# connectors.net
KiCad netlist of a schematic drawn in EAGLE
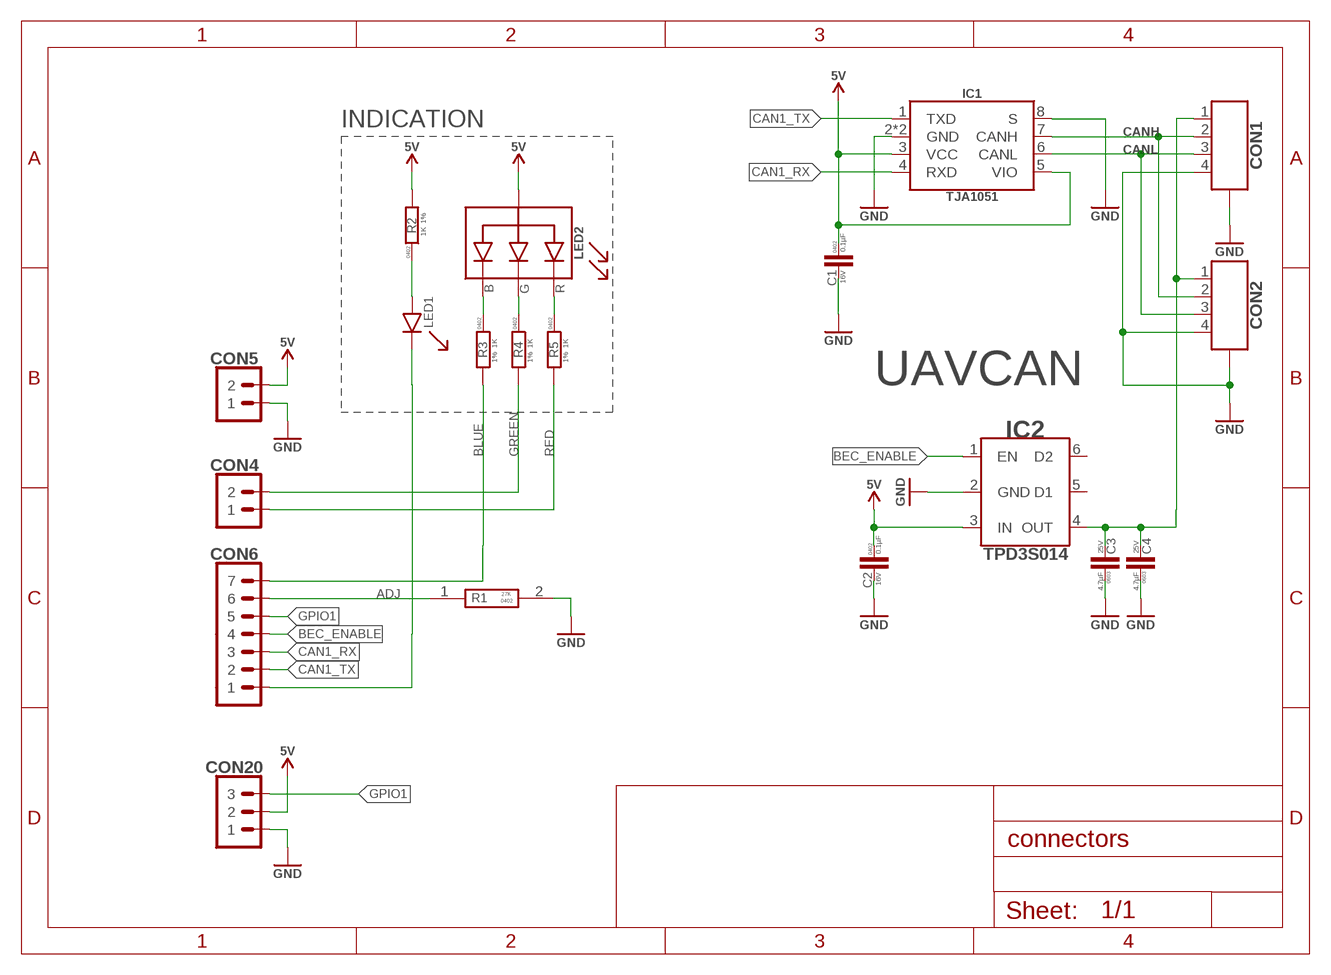
[diagram p0: schematic, sheet 1]

(export (version "E")
  (design (tool "Eeschema 10.0.6"))
  (components
    (comp (ref "C1")
      (value "0.1µF")
      (footprint "eagle-import:C0402")
      (fields
        (field (name "MANF") "Murata Electronics North America")
        (field (name "PACKAGE") "0402")
        (field (name "TOLERANCE") "+-10%")
        (field (name "VOLTAGE") "16V")
      )
      (libsource (lib "eagle-import") (part "0.1µF-0402-16V_10%_X7R"))
    )
    (comp (ref "C2")
      (value "0.1µF")
      (footprint "eagle-import:C0402")
      (fields
        (field (name "MANF") "Murata Electronics North America")
        (field (name "PACKAGE") "0402")
        (field (name "TOLERANCE") "+-10%")
        (field (name "VOLTAGE") "16V")
      )
      (libsource (lib "eagle-import") (part "0.1µF-0402-16V_10%_X7R"))
    )
    (comp (ref "C3")
      (value "4.7µF")
      (footprint "eagle-import:C0603")
      (fields
        (field (name "MANF") "Murata Electronics North America")
        (field (name "PACKAGE") "0603")
        (field (name "TOLERANCE") "+-10%")
        (field (name "VOLTAGE") "25V")
      )
      (libsource (lib "eagle-import") (part "4.7µF-0603-25V_10%_X6S"))
    )
    (comp (ref "C4")
      (value "4.7µF")
      (footprint "eagle-import:C0603")
      (fields
        (field (name "MANF") "Murata Electronics North America")
        (field (name "PACKAGE") "0603")
        (field (name "TOLERANCE") "+-10%")
        (field (name "VOLTAGE") "25V")
      )
      (libsource (lib "eagle-import") (part "4.7µF-0603-25V_10%_X6S"))
    )
    (comp (ref "CON1")
      (value "CON-4P-TABS-JST_GH-RA")
      (footprint "eagle-import:JST_GH-4P-RA")
      (fields (field (name "MANF") "JST Sales America Inc"))
      (libsource (lib "eagle-import") (part "CON-4P-TABS-RA-JST_GH"))
    )
    (comp (ref "CON2")
      (value "CON-4P-TABS-JST_GH-RA")
      (footprint "eagle-import:JST_GH-4P-RA")
      (fields (field (name "MANF") "JST Sales America Inc"))
      (libsource (lib "eagle-import") (part "CON-4P-TABS-RA-JST_GH"))
    )
    (comp (ref "CON4")
      (value "PINHEAD_1X02-2")
      (footprint "eagle-import:1X02-PTH-2")
      (libsource (lib "eagle-import") (part "PINHEAD_1X02-2"))
    )
    (comp (ref "CON5")
      (value "PINHEAD_1X02-2")
      (footprint "eagle-import:1X02-PTH-2")
      (libsource (lib "eagle-import") (part "PINHEAD_1X02-2"))
    )
    (comp (ref "CON6")
      (value "PINHEAD_1X07-2")
      (footprint "eagle-import:1X07-PTH-2")
      (libsource (lib "eagle-import") (part "PINHEAD_1X07-2"))
    )
    (comp (ref "CON20")
      (value "PINHEAD_1X03-2.54-RA")
      (footprint "eagle-import:1X03-PTH-2.54-RA")
      (libsource (lib "eagle-import") (part "PINHEAD_1X03-2.54-RA"))
    )
    (comp (ref "IC1")
      (value "TJA1051")
      (footprint "eagle-import:SOT782-1")
      (fields (field (name "MANF") "NXP Semiconductors"))
      (libsource (lib "eagle-import") (part "TJA1051"))
    )
    (comp (ref "IC2")
      (value "TPD3S014DBVR-SOT23-6")
      (footprint "eagle-import:SOT26")
      (fields (field (name "MANF") "Texas Instruments"))
      (libsource (lib "eagle-import") (part "TPD3S014DBVR-SOT23-6"))
    )
    (comp (ref "LED1")
      (value "GREEN")
      (footprint "eagle-import:0402_LED")
      (fields (field (name "MANF") "Rohm Semiconductor"))
      (libsource (lib "eagle-import") (part "LED-0402-GREEN"))
    )
    (comp (ref "LED2")
      (value "LTST-C19HE1WT")
      (footprint "eagle-import:LITE_ON_RGB_LED")
      (fields (field (name "MANF") "Lite-On Inc"))
      (libsource (lib "eagle-import") (part "LTST-C19HE1WT"))
    )
    (comp (ref "R1")
      (value "27K")
      (footprint "eagle-import:RESC1005X40N")
      (description "YAGEO - AF0402FR-0727KL - SMD Chip Resistor, 27 kohm, +/- 1%, 62.5 mW, 0402 [1005 Metric], Thick Film, General Purpose")
      (fields
        (field (name "MANUFACTURER_PART_NUMBER") "RC0402FR-0727KL")
        (field (name "HEIGHT") "0.32mm")
        (field (name "MANF") "YAGEO")
        (field (name "MANUFACTURER_PART_NUMBER_1") "AF0402FR-0727KL")
        (field (name "PACKAGE") "0402")
      )
      (libsource (lib "eagle-import") (part "RC0402FR-0727KL"))
    )
    (comp (ref "R2")
      (value "1K")
      (footprint "eagle-import:R0402")
      (fields (field (name "MANF") "Yageo") (field (name "PACKAGE") "0402") (field (name "TOLERANCE") "1%"))
      (libsource (lib "eagle-import") (part "1K-0402-1%"))
    )
    (comp (ref "R3")
      (value "1K")
      (footprint "eagle-import:R0402")
      (fields (field (name "MANF") "Yageo") (field (name "PACKAGE") "0402") (field (name "TOLERANCE") "1%"))
      (libsource (lib "eagle-import") (part "1K-0402-1%"))
    )
    (comp (ref "R4")
      (value "1K")
      (footprint "eagle-import:R0402")
      (fields (field (name "MANF") "Yageo") (field (name "PACKAGE") "0402") (field (name "TOLERANCE") "1%"))
      (libsource (lib "eagle-import") (part "1K-0402-1%"))
    )
    (comp (ref "R5")
      (value "1K")
      (footprint "eagle-import:R0402")
      (fields (field (name "MANF") "Yageo") (field (name "PACKAGE") "0402") (field (name "TOLERANCE") "1%"))
      (libsource (lib "eagle-import") (part "1K-0402-1%"))
    )
  )
  (nets
    (net (code "1") (name "/ADJ") (class "Default")
      (node (ref "CON6") (pin "6") (pinfunction "6_6") (pintype "passive"))
      (node (ref "R1") (pin "1") (pinfunction "1_1") (pintype "bidirectional"))
    )
    (net (code "2") (name "/BLUE") (class "Default")
      (node (ref "CON6") (pin "7") (pinfunction "7_7") (pintype "passive"))
      (node (ref "R3") (pin "2") (pinfunction "2_2") (pintype "passive"))
    )
    (net (code "3") (name "/CANH") (class "Default")
      (node (ref "CON1") (pin "2") (pinfunction "2_2") (pintype "bidirectional"))
      (node (ref "CON2") (pin "2") (pinfunction "2_2") (pintype "bidirectional"))
      (node (ref "IC1") (pin "7") (pinfunction "CANH_7") (pintype "bidirectional"))
    )
    (net (code "4") (name "/CANL") (class "Default")
      (node (ref "CON1") (pin "3") (pinfunction "3_3") (pintype "bidirectional"))
      (node (ref "CON2") (pin "3") (pinfunction "3_3") (pintype "bidirectional"))
      (node (ref "IC1") (pin "6") (pinfunction "CANL_6") (pintype "bidirectional"))
    )
    (net (code "5") (name "/GREEN") (class "Default")
      (node (ref "CON4") (pin "2") (pinfunction "2_2") (pintype "passive"))
      (node (ref "R4") (pin "2") (pinfunction "2_2") (pintype "passive"))
    )
    (net (code "6") (name "/RED") (class "Default")
      (node (ref "CON4") (pin "1") (pinfunction "1_1") (pintype "passive"))
      (node (ref "R5") (pin "2") (pinfunction "2_2") (pintype "passive"))
    )
    (net (code "7") (name "5V") (class "Default")
      (node (ref "C1") (pin "1") (pinfunction "1_1") (pintype "passive"))
      (node (ref "C2") (pin "1") (pinfunction "1_1") (pintype "passive"))
      (node (ref "CON20") (pin "2") (pinfunction "2_2") (pintype "passive"))
      (node (ref "CON5") (pin "2") (pinfunction "2_2") (pintype "passive"))
      (node (ref "IC1") (pin "3") (pinfunction "VCC_3") (pintype "bidirectional"))
      (node (ref "IC1") (pin "5") (pinfunction "VIO_5") (pintype "bidirectional"))
      (node (ref "IC2") (pin "3") (pinfunction "IN_3") (pintype "bidirectional"))
      (node (ref "LED2") (pin "+") (pinfunction "A_+") (pintype "bidirectional"))
      (node (ref "R2") (pin "2") (pinfunction "2_2") (pintype "passive"))
    )
    (net (code "8") (name "BEC_ENABLE") (class "Default")
      (node (ref "CON6") (pin "4") (pinfunction "4_4") (pintype "passive"))
      (node (ref "IC2") (pin "1") (pinfunction "EN_1") (pintype "bidirectional"))
    )
    (net (code "9") (name "CAN1_RX") (class "Default")
      (node (ref "CON6") (pin "3") (pinfunction "3_3") (pintype "passive"))
      (node (ref "IC1") (pin "4") (pinfunction "RXD_4") (pintype "bidirectional"))
    )
    (net (code "10") (name "CAN1_TX") (class "Default")
      (node (ref "CON6") (pin "2") (pinfunction "2_2") (pintype "passive"))
      (node (ref "IC1") (pin "1") (pinfunction "TXD_1") (pintype "bidirectional"))
    )
    (net (code "11") (name "GND") (class "Default")
      (node (ref "C1") (pin "2") (pinfunction "2_2") (pintype "passive"))
      (node (ref "C2") (pin "2") (pinfunction "2_2") (pintype "passive"))
      (node (ref "C3") (pin "P$1") (pinfunction "1_P$1") (pintype "passive"))
      (node (ref "C4") (pin "P$1") (pinfunction "1_P$1") (pintype "passive"))
      (node (ref "CON1") (pin "4") (pinfunction "4_4") (pintype "bidirectional"))
      (node (ref "CON1") (pin "M$0") (pinfunction "GND_M$0") (pintype "bidirectional"))
      (node (ref "CON1") (pin "M$1") (pinfunction "GND_M$1") (pintype "bidirectional"))
      (node (ref "CON2") (pin "4") (pinfunction "4_4") (pintype "bidirectional"))
      (node (ref "CON2") (pin "M$0") (pinfunction "GND_M$0") (pintype "bidirectional"))
      (node (ref "CON2") (pin "M$1") (pinfunction "GND_M$1") (pintype "bidirectional"))
      (node (ref "CON20") (pin "1") (pinfunction "1_1") (pintype "passive"))
      (node (ref "CON5") (pin "1") (pinfunction "1_1") (pintype "passive"))
      (node (ref "IC1") (pin "2") (pinfunction "GND_2") (pintype "bidirectional"))
      (node (ref "IC1") (pin "8") (pinfunction "S_8") (pintype "bidirectional"))
      (node (ref "IC1") (pin "PAD") (pinfunction "GND_PAD") (pintype "bidirectional"))
      (node (ref "IC2") (pin "2") (pinfunction "GND_2") (pintype "bidirectional"))
      (node (ref "R1") (pin "2") (pinfunction "2_2") (pintype "bidirectional"))
    )
    (net (code "12") (name "GPIO1") (class "Default")
      (node (ref "CON20") (pin "3") (pinfunction "3_3") (pintype "passive"))
      (node (ref "CON6") (pin "5") (pinfunction "5_5") (pintype "passive"))
    )
    (net (code "13") (name "Net-(C3-2)") (class "Default")
      (node (ref "C3") (pin "P$2") (pinfunction "2_P$2") (pintype "passive"))
      (node (ref "C4") (pin "P$2") (pinfunction "2_P$2") (pintype "passive"))
      (node (ref "CON1") (pin "1") (pinfunction "1_1") (pintype "bidirectional"))
      (node (ref "CON2") (pin "1") (pinfunction "1_1") (pintype "bidirectional"))
      (node (ref "IC2") (pin "4") (pinfunction "OUT_4") (pintype "bidirectional"))
    )
    (net (code "14") (name "Net-(CON6-Pad1)") (class "Default")
      (node (ref "CON6") (pin "1") (pinfunction "1_1") (pintype "passive"))
      (node (ref "LED1") (pin "C") (pinfunction "C_C") (pintype "bidirectional"))
    )
    (net (code "15") (name "Net-(LED1-PadA)") (class "Default")
      (node (ref "LED1") (pin "A") (pinfunction "A_A") (pintype "bidirectional"))
      (node (ref "R2") (pin "1") (pinfunction "1_1") (pintype "passive"))
    )
    (net (code "16") (name "Net-(LED2-PadB)") (class "Default")
      (node (ref "LED2") (pin "B") (pinfunction "B_B") (pintype "bidirectional"))
      (node (ref "R3") (pin "1") (pinfunction "1_1") (pintype "passive"))
    )
    (net (code "17") (name "Net-(LED2-PadG)") (class "Default")
      (node (ref "LED2") (pin "G") (pinfunction "G_G") (pintype "bidirectional"))
      (node (ref "R4") (pin "1") (pinfunction "1_1") (pintype "passive"))
    )
    (net (code "18") (name "Net-(LED2-PadR)") (class "Default")
      (node (ref "LED2") (pin "R") (pinfunction "R_R") (pintype "bidirectional"))
      (node (ref "R5") (pin "1") (pinfunction "1_1") (pintype "passive"))
    )
    (net (code "19") (name "unconnected-(IC2-D1-Pad5)") (class "Default")
      (node (ref "IC2") (pin "5") (pinfunction "D1_5") (pintype "bidirectional"))
    )
    (net (code "20") (name "unconnected-(IC2-D2-Pad6)") (class "Default")
      (node (ref "IC2") (pin "6") (pinfunction "D2_6") (pintype "bidirectional"))
    )
  )
)
